# FidoComm.net
KiCad netlist of a schematic drawn in EAGLE
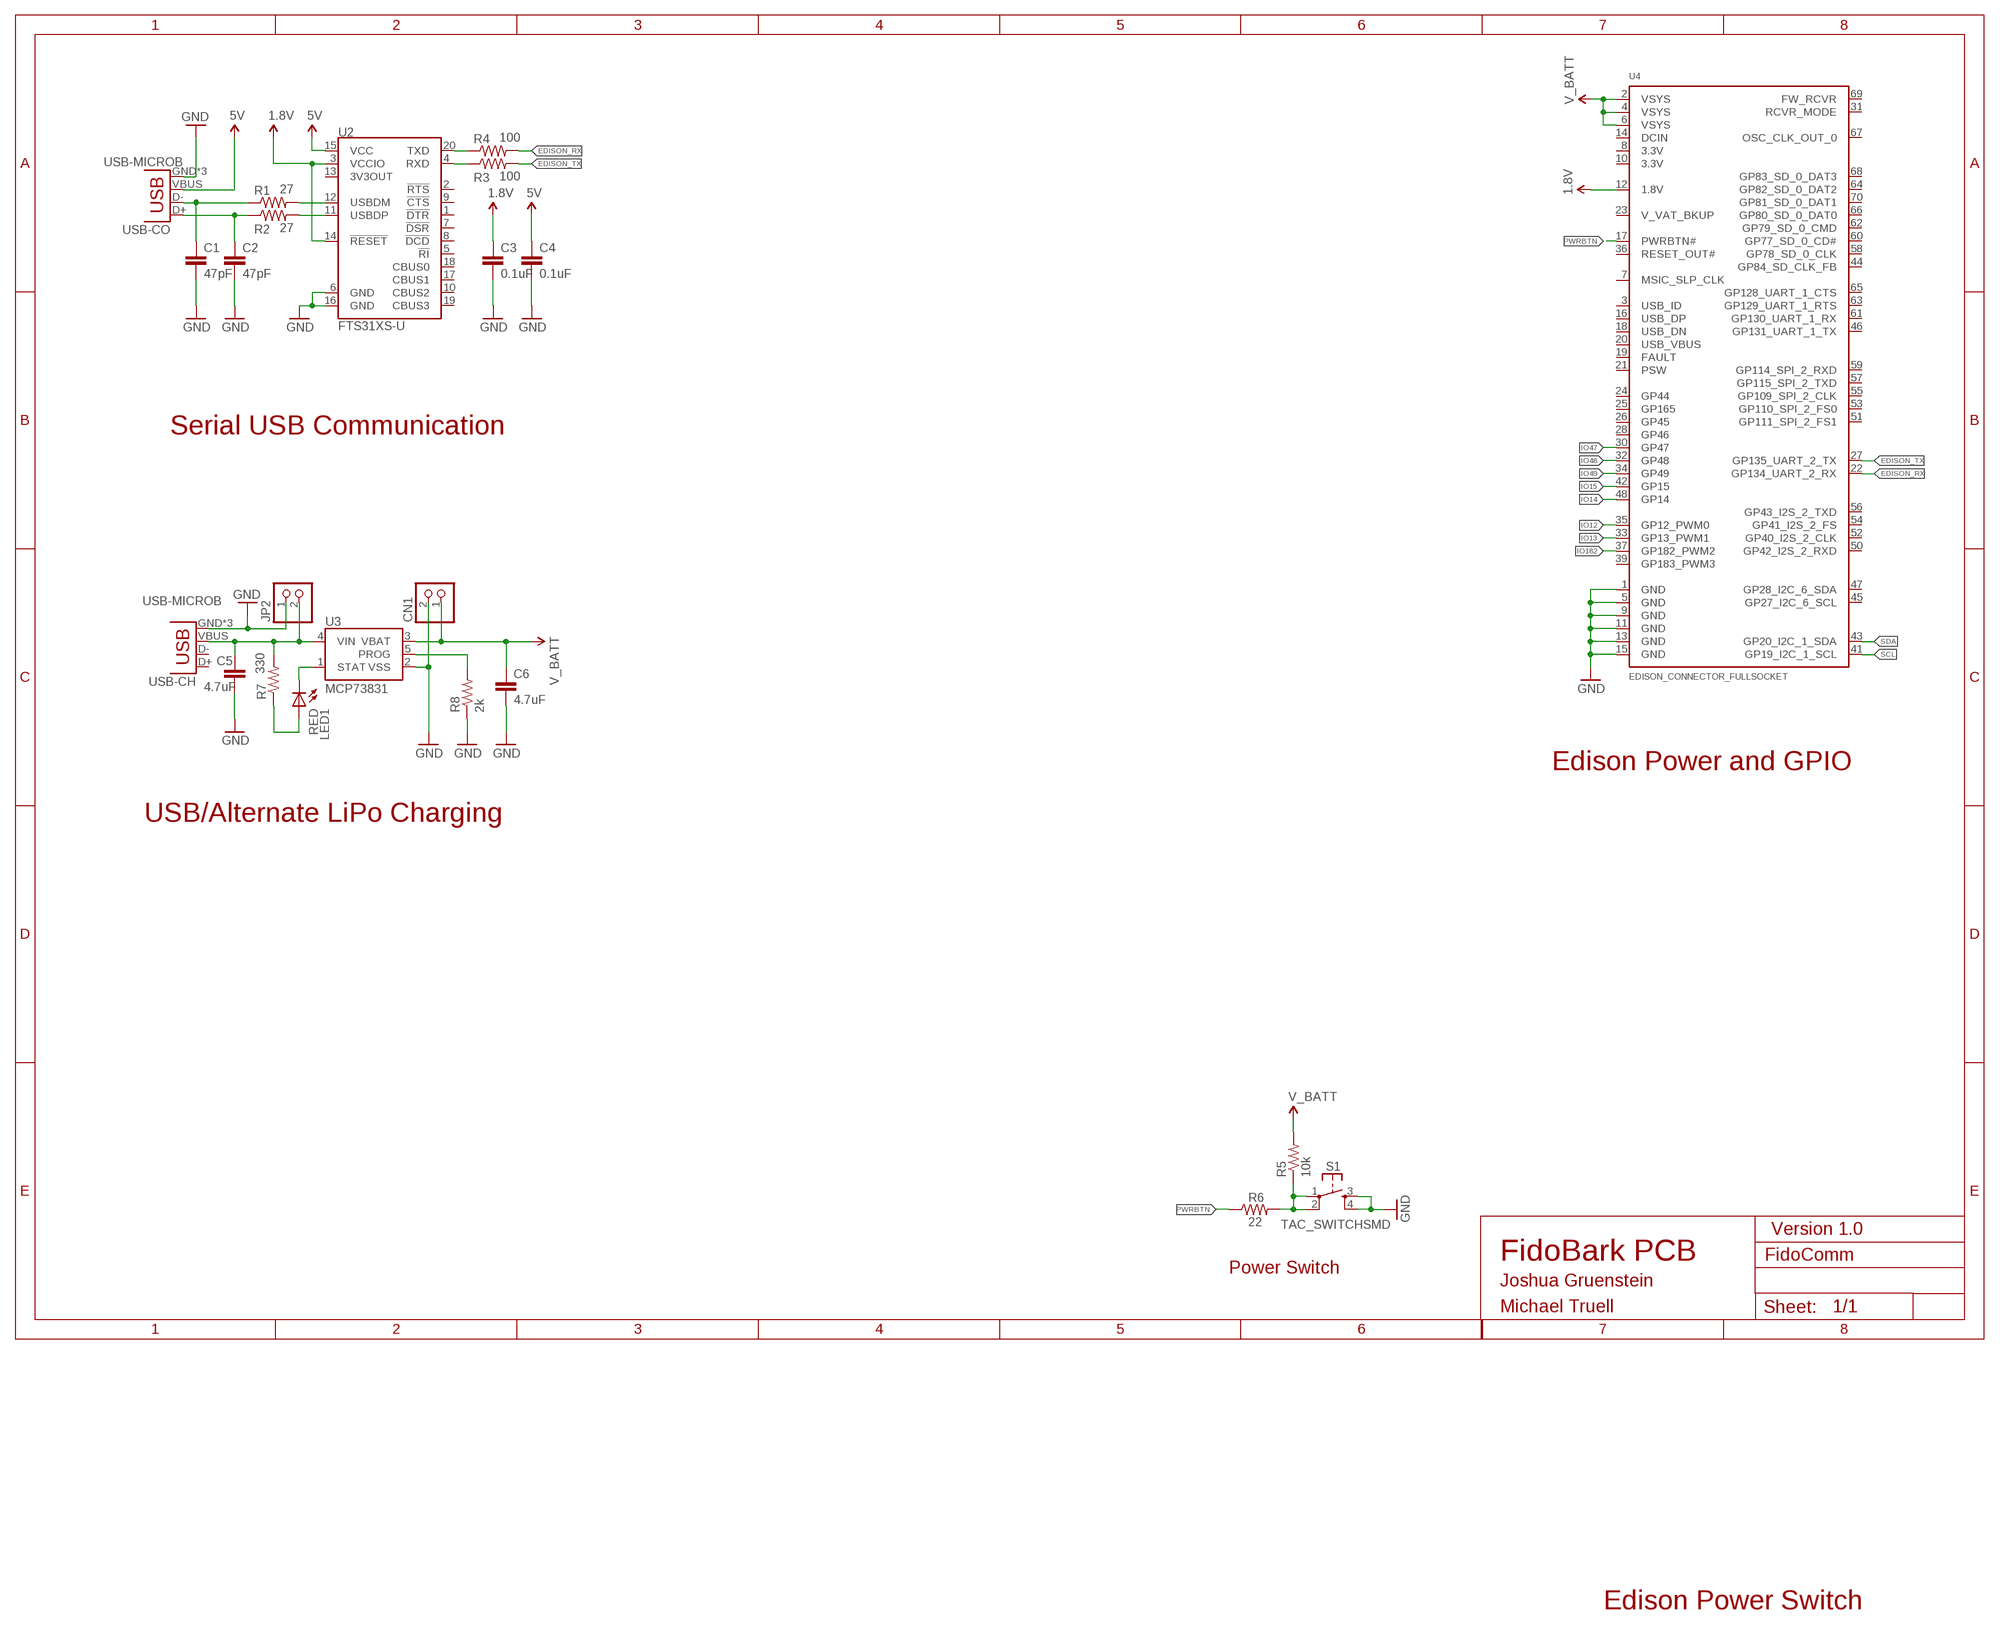
[diagram p0: schematic, sheet 1]

(export (version "E")
  (design (tool "Eeschema 10.0.6"))
  (components
    (comp (ref "C1")
      (value "47pF")
      (footprint "eagle-import:0603-CAP")
      (libsource (lib "eagle-import") (part "CAP0603-CAP"))
    )
    (comp (ref "C2")
      (value "47pF")
      (footprint "eagle-import:0603-CAP")
      (libsource (lib "eagle-import") (part "CAP0603-CAP"))
    )
    (comp (ref "C3")
      (value "0.1uF")
      (footprint "eagle-import:0603-CAP")
      (libsource (lib "eagle-import") (part "CAP0603-CAP"))
    )
    (comp (ref "C4")
      (value "0.1uF")
      (footprint "eagle-import:0603-CAP")
      (libsource (lib "eagle-import") (part "CAP0603-CAP"))
    )
    (comp (ref "C5")
      (value "4.7uF")
      (footprint "eagle-import:0603-CAP")
      (libsource (lib "eagle-import") (part "CAP0603-CAP"))
    )
    (comp (ref "C6")
      (value "4.7uF")
      (footprint "eagle-import:0603-CAP")
      (libsource (lib "eagle-import") (part "CAP0603-CAP"))
    )
    (comp (ref "CN1")
      (value "JST_2PIN-SMT-RA")
      (footprint "eagle-import:JST-PH-2-SMT-RA")
      (libsource (lib "eagle-import") (part "JST_2PIN-SMT-RA"))
    )
    (comp (ref "JP2")
      (value "PINHD-1X2")
      (footprint "eagle-import:1X02")
      (libsource (lib "eagle-import") (part "PINHD-1X2"))
    )
    (comp (ref "LED1")
      (value "RED")
      (footprint "eagle-import:CHIP-LED0603")
      (libsource (lib "eagle-import") (part "LEDCHIP-LED0603"))
    )
    (comp (ref "R1")
      (value "27")
      (footprint "eagle-import:R0603")
      (libsource (lib "eagle-import") (part "R-US_R0603"))
    )
    (comp (ref "R2")
      (value "27")
      (footprint "eagle-import:R0603")
      (libsource (lib "eagle-import") (part "R-US_R0603"))
    )
    (comp (ref "R3")
      (value "100")
      (footprint "eagle-import:R0603")
      (libsource (lib "eagle-import") (part "R-US_R0603"))
    )
    (comp (ref "R4")
      (value "100")
      (footprint "eagle-import:R0603")
      (libsource (lib "eagle-import") (part "R-US_R0603"))
    )
    (comp (ref "R5")
      (value "10k")
      (footprint "eagle-import:R0603")
      (libsource (lib "eagle-import") (part "R-US_R0603"))
    )
    (comp (ref "R6")
      (value "22")
      (footprint "eagle-import:R0603")
      (libsource (lib "eagle-import") (part "R-US_R0603"))
    )
    (comp (ref "R7")
      (value "330")
      (footprint "eagle-import:R0603")
      (libsource (lib "eagle-import") (part "R-US_R0603"))
    )
    (comp (ref "R8")
      (value "2k")
      (footprint "eagle-import:R0603")
      (libsource (lib "eagle-import") (part "R-US_R0603"))
    )
    (comp (ref "S1")
      (value "TAC_SWITCHSMD")
      (footprint "eagle-import:TACTILE-SWITCH-SMD")
      (libsource (lib "eagle-import") (part "TAC_SWITCHSMD"))
    )
    (comp (ref "U2")
      (value "FTS31XS-U")
      (footprint "eagle-import:SSOP20_L")
      (libsource (lib "eagle-import") (part "FT231XS"))
    )
    (comp (ref "U3")
      (value "MCP73831")
      (footprint "eagle-import:SOT23-5")
      (libsource (lib "eagle-import") (part "MCP73831"))
    )
    (comp (ref "U4")
      (value "EDISON_CONNECTOR_FULLSOCKET")
      (footprint "eagle-import:DF40-XC-(X.X)-70DS-0.4V(51)")
      (libsource (lib "eagle-import") (part "EDISON_CONNECTOR_FULLSOCKET"))
    )
    (comp (ref "USB-CH")
      (value "USB-MICROB")
      (footprint "eagle-import:USB-MICROB")
      (libsource (lib "eagle-import") (part "USB-MICROB"))
    )
    (comp (ref "USB-CO")
      (value "USB-MICROB")
      (footprint "eagle-import:USB-MICROB")
      (libsource (lib "eagle-import") (part "USB-MICROB"))
    )
  )
  (nets
    (net (code "1") (name "1.8V") (class "Default")
      (node (ref "C3") (pin "1") (pinfunction "1_1") (pintype "passive"))
      (node (ref "U2") (pin "14") (pinfunction "~{RESET}_14") (pintype "bidirectional"))
      (node (ref "U2") (pin "3") (pinfunction "VCCIO_3") (pintype "bidirectional"))
      (node (ref "U4") (pin "12") (pinfunction "1.8V_12") (pintype "bidirectional"))
    )
    (net (code "2") (name "5V") (class "Default")
      (node (ref "C4") (pin "1") (pinfunction "1_1") (pintype "passive"))
      (node (ref "U2") (pin "15") (pinfunction "VCC_15") (pintype "bidirectional"))
      (node (ref "USB-CO") (pin "VBUS") (pinfunction "VBUS_VBUS") (pintype "bidirectional"))
    )
    (net (code "3") (name "EDISON_RX") (class "Default")
      (node (ref "R4") (pin "2") (pinfunction "2_2") (pintype "passive"))
      (node (ref "U4") (pin "22") (pinfunction "GP134_UART_2_RX_22") (pintype "bidirectional"))
    )
    (net (code "4") (name "EDISON_TX") (class "Default")
      (node (ref "R3") (pin "2") (pinfunction "2_2") (pintype "passive"))
      (node (ref "U4") (pin "27") (pinfunction "GP135_UART_2_TX_27") (pintype "bidirectional"))
    )
    (net (code "5") (name "GND") (class "Default")
      (node (ref "C1") (pin "2") (pinfunction "2_2") (pintype "passive"))
      (node (ref "C2") (pin "2") (pinfunction "2_2") (pintype "passive"))
      (node (ref "C3") (pin "2") (pinfunction "2_2") (pintype "passive"))
      (node (ref "C4") (pin "2") (pinfunction "2_2") (pintype "passive"))
      (node (ref "C5") (pin "2") (pinfunction "2_2") (pintype "passive"))
      (node (ref "C6") (pin "2") (pinfunction "2_2") (pintype "passive"))
      (node (ref "CN1") (pin "2") (pinfunction "1_2") (pintype "passive"))
      (node (ref "JP2") (pin "1") (pinfunction "1_1") (pintype "passive"))
      (node (ref "R8") (pin "1") (pinfunction "1_1") (pintype "passive"))
      (node (ref "S1") (pin "3") (pinfunction "3_3") (pintype "passive"))
      (node (ref "S1") (pin "4") (pinfunction "4_4") (pintype "passive"))
      (node (ref "U2") (pin "16") (pinfunction "GND_16") (pintype "bidirectional"))
      (node (ref "U2") (pin "6") (pinfunction "GND_6") (pintype "bidirectional"))
      (node (ref "U3") (pin "2") (pinfunction "VSS_2") (pintype "power_in"))
      (node (ref "U4") (pin "1") (pinfunction "GND_1") (pintype "bidirectional"))
      (node (ref "U4") (pin "11") (pinfunction "GND_11") (pintype "bidirectional"))
      (node (ref "U4") (pin "13") (pinfunction "GND_13") (pintype "bidirectional"))
      (node (ref "U4") (pin "15") (pinfunction "GND_15") (pintype "bidirectional"))
      (node (ref "U4") (pin "5") (pinfunction "GND_5") (pintype "bidirectional"))
      (node (ref "U4") (pin "9") (pinfunction "GND_9") (pintype "bidirectional"))
      (node (ref "USB-CH") (pin "GND") (pinfunction "GND_GND") (pintype "bidirectional"))
      (node (ref "USB-CH") (pin "MT1") (pinfunction "GND_MT1") (pintype "bidirectional"))
      (node (ref "USB-CH") (pin "MT2") (pinfunction "GND_MT2") (pintype "bidirectional"))
      (node (ref "USB-CO") (pin "GND") (pinfunction "GND_GND") (pintype "bidirectional"))
      (node (ref "USB-CO") (pin "MT1") (pinfunction "GND_MT1") (pintype "bidirectional"))
      (node (ref "USB-CO") (pin "MT2") (pinfunction "GND_MT2") (pintype "bidirectional"))
    )
    (net (code "6") (name "IO12") (class "Default")
      (node (ref "U4") (pin "35") (pinfunction "GP12_PWM0_35") (pintype "bidirectional"))
    )
    (net (code "7") (name "IO13") (class "Default")
      (node (ref "U4") (pin "33") (pinfunction "GP13_PWM1_33") (pintype "bidirectional"))
    )
    (net (code "8") (name "IO14") (class "Default")
      (node (ref "U4") (pin "48") (pinfunction "GP14_48") (pintype "bidirectional"))
    )
    (net (code "9") (name "IO15") (class "Default")
      (node (ref "U4") (pin "42") (pinfunction "GP15_42") (pintype "bidirectional"))
    )
    (net (code "10") (name "IO47") (class "Default")
      (node (ref "U4") (pin "30") (pinfunction "GP47_30") (pintype "bidirectional"))
    )
    (net (code "11") (name "IO48") (class "Default")
      (node (ref "U4") (pin "32") (pinfunction "GP48_32") (pintype "bidirectional"))
    )
    (net (code "12") (name "IO49") (class "Default")
      (node (ref "U4") (pin "34") (pinfunction "GP49_34") (pintype "bidirectional"))
    )
    (net (code "13") (name "IO182") (class "Default")
      (node (ref "U4") (pin "37") (pinfunction "GP182_PWM2_37") (pintype "bidirectional"))
    )
    (net (code "14") (name "Net-(C1-Pad1)") (class "Default")
      (node (ref "C1") (pin "1") (pinfunction "1_1") (pintype "passive"))
      (node (ref "R1") (pin "1") (pinfunction "1_1") (pintype "passive"))
      (node (ref "USB-CO") (pin "D-") (pinfunction "D-_D-") (pintype "bidirectional"))
    )
    (net (code "15") (name "Net-(C2-Pad1)") (class "Default")
      (node (ref "C2") (pin "1") (pinfunction "1_1") (pintype "passive"))
      (node (ref "R2") (pin "1") (pinfunction "1_1") (pintype "passive"))
      (node (ref "USB-CO") (pin "D+") (pinfunction "D+_D+") (pintype "bidirectional"))
    )
    (net (code "16") (name "Net-(LED1-PadA)") (class "Default")
      (node (ref "LED1") (pin "A") (pinfunction "A_A") (pintype "passive"))
      (node (ref "R7") (pin "1") (pinfunction "1_1") (pintype "passive"))
    )
    (net (code "17") (name "Net-(R5-Pad1)") (class "Default")
      (node (ref "R5") (pin "1") (pinfunction "1_1") (pintype "passive"))
      (node (ref "R6") (pin "2") (pinfunction "2_2") (pintype "passive"))
      (node (ref "S1") (pin "1") (pinfunction "1_1") (pintype "passive"))
      (node (ref "S1") (pin "2") (pinfunction "2_2") (pintype "passive"))
    )
    (net (code "18") (name "Net-(U2-RXD)") (class "Default")
      (node (ref "R3") (pin "1") (pinfunction "1_1") (pintype "passive"))
      (node (ref "U2") (pin "4") (pinfunction "RXD_4") (pintype "bidirectional"))
    )
    (net (code "19") (name "Net-(U2-TXD)") (class "Default")
      (node (ref "R4") (pin "1") (pinfunction "1_1") (pintype "passive"))
      (node (ref "U2") (pin "20") (pinfunction "TXD_20") (pintype "bidirectional"))
    )
    (net (code "20") (name "Net-(U2-USBDM)") (class "Default")
      (node (ref "R1") (pin "2") (pinfunction "2_2") (pintype "passive"))
      (node (ref "U2") (pin "12") (pinfunction "USBDM_12") (pintype "bidirectional"))
    )
    (net (code "21") (name "Net-(U2-USBDP)") (class "Default")
      (node (ref "R2") (pin "2") (pinfunction "2_2") (pintype "passive"))
      (node (ref "U2") (pin "11") (pinfunction "USBDP_11") (pintype "bidirectional"))
    )
    (net (code "22") (name "Net-(U3-PROG)") (class "Default")
      (node (ref "R8") (pin "2") (pinfunction "2_2") (pintype "passive"))
      (node (ref "U3") (pin "5") (pinfunction "PROG_5") (pintype "input"))
    )
    (net (code "23") (name "Net-(U3-STAT)") (class "Default")
      (node (ref "LED1") (pin "C") (pinfunction "C_C") (pintype "passive"))
      (node (ref "U3") (pin "1") (pinfunction "STAT_1") (pintype "output"))
    )
    (net (code "24") (name "Net-(U3-VIN)") (class "Default")
      (node (ref "C5") (pin "1") (pinfunction "1_1") (pintype "passive"))
      (node (ref "JP2") (pin "2") (pinfunction "2_2") (pintype "passive"))
      (node (ref "R7") (pin "2") (pinfunction "2_2") (pintype "passive"))
      (node (ref "U3") (pin "4") (pinfunction "VIN_4") (pintype "power_in"))
      (node (ref "USB-CH") (pin "VBUS") (pinfunction "VBUS_VBUS") (pintype "bidirectional"))
    )
    (net (code "25") (name "PWRBTN") (class "Default")
      (node (ref "R6") (pin "1") (pinfunction "1_1") (pintype "passive"))
      (node (ref "U4") (pin "17") (pinfunction "PWRBTN#_17") (pintype "bidirectional"))
    )
    (net (code "26") (name "SCL") (class "Default")
      (node (ref "U4") (pin "41") (pinfunction "GP19_I2C_1_SCL_41") (pintype "bidirectional"))
    )
    (net (code "27") (name "SDA") (class "Default")
      (node (ref "U4") (pin "43") (pinfunction "GP20_I2C_1_SDA_43") (pintype "bidirectional"))
    )
    (net (code "28") (name "V_BATT") (class "Default")
      (node (ref "C6") (pin "1") (pinfunction "1_1") (pintype "passive"))
      (node (ref "CN1") (pin "1") (pinfunction "2_1") (pintype "passive"))
      (node (ref "R5") (pin "2") (pinfunction "2_2") (pintype "passive"))
      (node (ref "U3") (pin "3") (pinfunction "VBAT_3") (pintype "power_in"))
      (node (ref "U4") (pin "2") (pinfunction "VSYS_2") (pintype "bidirectional"))
      (node (ref "U4") (pin "4") (pinfunction "VSYS_4") (pintype "bidirectional"))
      (node (ref "U4") (pin "6") (pinfunction "VSYS_6") (pintype "bidirectional"))
    )
    (net (code "29") (name "unconnected-(U2-3V3OUT-Pad13)") (class "Default")
      (node (ref "U2") (pin "13") (pinfunction "3V3OUT_13") (pintype "bidirectional"))
    )
    (net (code "30") (name "unconnected-(U2-CBUS0-Pad18)") (class "Default")
      (node (ref "U2") (pin "18") (pinfunction "CBUS0_18") (pintype "bidirectional"))
    )
    (net (code "31") (name "unconnected-(U2-CBUS1-Pad17)") (class "Default")
      (node (ref "U2") (pin "17") (pinfunction "CBUS1_17") (pintype "bidirectional"))
    )
    (net (code "32") (name "unconnected-(U2-CBUS2-Pad10)") (class "Default")
      (node (ref "U2") (pin "10") (pinfunction "CBUS2_10") (pintype "bidirectional"))
    )
    (net (code "33") (name "unconnected-(U2-CBUS3-Pad19)") (class "Default")
      (node (ref "U2") (pin "19") (pinfunction "CBUS3_19") (pintype "bidirectional"))
    )
    (net (code "34") (name "unconnected-(U2-~{CTS}-Pad9)") (class "Default")
      (node (ref "U2") (pin "9") (pinfunction "~{CTS}_9") (pintype "bidirectional"))
    )
    (net (code "35") (name "unconnected-(U2-~{DCD}-Pad8)") (class "Default")
      (node (ref "U2") (pin "8") (pinfunction "~{DCD}_8") (pintype "bidirectional"))
    )
    (net (code "36") (name "unconnected-(U2-~{DSR}-Pad7)") (class "Default")
      (node (ref "U2") (pin "7") (pinfunction "~{DSR}_7") (pintype "bidirectional"))
    )
    (net (code "37") (name "unconnected-(U2-~{DTR}-Pad1)") (class "Default")
      (node (ref "U2") (pin "1") (pinfunction "~{DTR}_1") (pintype "bidirectional"))
    )
    (net (code "38") (name "unconnected-(U2-~{RI}-Pad5)") (class "Default")
      (node (ref "U2") (pin "5") (pinfunction "~{RI}_5") (pintype "bidirectional"))
    )
    (net (code "39") (name "unconnected-(U2-~{RTS}-Pad2)") (class "Default")
      (node (ref "U2") (pin "2") (pinfunction "~{RTS}_2") (pintype "bidirectional"))
    )
    (net (code "40") (name "unconnected-(U4-3.3V-Pad8)") (class "Default")
      (node (ref "U4") (pin "8") (pinfunction "3.3V_8") (pintype "bidirectional"))
    )
    (net (code "41") (name "unconnected-(U4-3.3V-Pad10)") (class "Default")
      (node (ref "U4") (pin "10") (pinfunction "3.3V_10") (pintype "bidirectional"))
    )
    (net (code "42") (name "unconnected-(U4-DCIN-Pad14)") (class "Default")
      (node (ref "U4") (pin "14") (pinfunction "DCIN_14") (pintype "bidirectional"))
    )
    (net (code "43") (name "unconnected-(U4-FAULT-Pad19)") (class "Default")
      (node (ref "U4") (pin "19") (pinfunction "FAULT_19") (pintype "bidirectional"))
    )
    (net (code "44") (name "unconnected-(U4-FW_RCVR-Pad69)") (class "Default")
      (node (ref "U4") (pin "69") (pinfunction "FW_RCVR_69") (pintype "bidirectional"))
    )
    (net (code "45") (name "unconnected-(U4-GP27_I2C_6_SCL-Pad45)") (class "Default")
      (node (ref "U4") (pin "45") (pinfunction "GP27_I2C_6_SCL_45") (pintype "bidirectional"))
    )
    (net (code "46") (name "unconnected-(U4-GP28_I2C_6_SDA-Pad47)") (class "Default")
      (node (ref "U4") (pin "47") (pinfunction "GP28_I2C_6_SDA_47") (pintype "bidirectional"))
    )
    (net (code "47") (name "unconnected-(U4-GP40_I2S_2_CLK-Pad52)") (class "Default")
      (node (ref "U4") (pin "52") (pinfunction "GP40_I2S_2_CLK_52") (pintype "bidirectional"))
    )
    (net (code "48") (name "unconnected-(U4-GP41_I2S_2_FS-Pad54)") (class "Default")
      (node (ref "U4") (pin "54") (pinfunction "GP41_I2S_2_FS_54") (pintype "bidirectional"))
    )
    (net (code "49") (name "unconnected-(U4-GP42_I2S_2_RXD-Pad50)") (class "Default")
      (node (ref "U4") (pin "50") (pinfunction "GP42_I2S_2_RXD_50") (pintype "bidirectional"))
    )
    (net (code "50") (name "unconnected-(U4-GP43_I2S_2_TXD-Pad56)") (class "Default")
      (node (ref "U4") (pin "56") (pinfunction "GP43_I2S_2_TXD_56") (pintype "bidirectional"))
    )
    (net (code "51") (name "unconnected-(U4-GP44-Pad24)") (class "Default")
      (node (ref "U4") (pin "24") (pinfunction "GP44_24") (pintype "bidirectional"))
    )
    (net (code "52") (name "unconnected-(U4-GP45-Pad26)") (class "Default")
      (node (ref "U4") (pin "26") (pinfunction "GP45_26") (pintype "bidirectional"))
    )
    (net (code "53") (name "unconnected-(U4-GP46-Pad28)") (class "Default")
      (node (ref "U4") (pin "28") (pinfunction "GP46_28") (pintype "bidirectional"))
    )
    (net (code "54") (name "unconnected-(U4-GP77_SD_0_CD#-Pad60)") (class "Default")
      (node (ref "U4") (pin "60") (pinfunction "GP77_SD_0_CD#_60") (pintype "bidirectional"))
    )
    (net (code "55") (name "unconnected-(U4-GP78_SD_0_CLK-Pad58)") (class "Default")
      (node (ref "U4") (pin "58") (pinfunction "GP78_SD_0_CLK_58") (pintype "bidirectional"))
    )
    (net (code "56") (name "unconnected-(U4-GP79_SD_0_CMD-Pad62)") (class "Default")
      (node (ref "U4") (pin "62") (pinfunction "GP79_SD_0_CMD_62") (pintype "bidirectional"))
    )
    (net (code "57") (name "unconnected-(U4-GP80_SD_0_DAT0-Pad66)") (class "Default")
      (node (ref "U4") (pin "66") (pinfunction "GP80_SD_0_DAT0_66") (pintype "bidirectional"))
    )
    (net (code "58") (name "unconnected-(U4-GP81_SD_0_DAT1-Pad70)") (class "Default")
      (node (ref "U4") (pin "70") (pinfunction "GP81_SD_0_DAT1_70") (pintype "bidirectional"))
    )
    (net (code "59") (name "unconnected-(U4-GP82_SD_0_DAT2-Pad64)") (class "Default")
      (node (ref "U4") (pin "64") (pinfunction "GP82_SD_0_DAT2_64") (pintype "bidirectional"))
    )
    (net (code "60") (name "unconnected-(U4-GP83_SD_0_DAT3-Pad68)") (class "Default")
      (node (ref "U4") (pin "68") (pinfunction "GP83_SD_0_DAT3_68") (pintype "bidirectional"))
    )
    (net (code "61") (name "unconnected-(U4-GP84_SD_CLK_FB-Pad44)") (class "Default")
      (node (ref "U4") (pin "44") (pinfunction "GP84_SD_CLK_FB_44") (pintype "bidirectional"))
    )
    (net (code "62") (name "unconnected-(U4-GP109_SPI_2_CLK-Pad55)") (class "Default")
      (node (ref "U4") (pin "55") (pinfunction "GP109_SPI_2_CLK_55") (pintype "bidirectional"))
    )
    (net (code "63") (name "unconnected-(U4-GP110_SPI_2_FS0-Pad53)") (class "Default")
      (node (ref "U4") (pin "53") (pinfunction "GP110_SPI_2_FS0_53") (pintype "bidirectional"))
    )
    (net (code "64") (name "unconnected-(U4-GP111_SPI_2_FS1-Pad51)") (class "Default")
      (node (ref "U4") (pin "51") (pinfunction "GP111_SPI_2_FS1_51") (pintype "bidirectional"))
    )
    (net (code "65") (name "unconnected-(U4-GP114_SPI_2_RXD-Pad59)") (class "Default")
      (node (ref "U4") (pin "59") (pinfunction "GP114_SPI_2_RXD_59") (pintype "bidirectional"))
    )
    (net (code "66") (name "unconnected-(U4-GP115_SPI_2_TXD-Pad57)") (class "Default")
      (node (ref "U4") (pin "57") (pinfunction "GP115_SPI_2_TXD_57") (pintype "bidirectional"))
    )
    (net (code "67") (name "unconnected-(U4-GP128_UART_1_CTS-Pad65)") (class "Default")
      (node (ref "U4") (pin "65") (pinfunction "GP128_UART_1_CTS_65") (pintype "bidirectional"))
    )
    (net (code "68") (name "unconnected-(U4-GP129_UART_1_RTS-Pad63)") (class "Default")
      (node (ref "U4") (pin "63") (pinfunction "GP129_UART_1_RTS_63") (pintype "bidirectional"))
    )
    (net (code "69") (name "unconnected-(U4-GP130_UART_1_RX-Pad61)") (class "Default")
      (node (ref "U4") (pin "61") (pinfunction "GP130_UART_1_RX_61") (pintype "bidirectional"))
    )
    (net (code "70") (name "unconnected-(U4-GP131_UART_1_TX-Pad46)") (class "Default")
      (node (ref "U4") (pin "46") (pinfunction "GP131_UART_1_TX_46") (pintype "bidirectional"))
    )
    (net (code "71") (name "unconnected-(U4-GP165-Pad25)") (class "Default")
      (node (ref "U4") (pin "25") (pinfunction "GP165_25") (pintype "bidirectional"))
    )
    (net (code "72") (name "unconnected-(U4-GP183_PWM3-Pad39)") (class "Default")
      (node (ref "U4") (pin "39") (pinfunction "GP183_PWM3_39") (pintype "bidirectional"))
    )
    (net (code "73") (name "unconnected-(U4-MSIC_SLP_CLK-Pad7)") (class "Default")
      (node (ref "U4") (pin "7") (pinfunction "MSIC_SLP_CLK_7") (pintype "bidirectional"))
    )
    (net (code "74") (name "unconnected-(U4-OSC_CLK_OUT_0-Pad67)") (class "Default")
      (node (ref "U4") (pin "67") (pinfunction "OSC_CLK_OUT_0_67") (pintype "bidirectional"))
    )
    (net (code "75") (name "unconnected-(U4-PSW-Pad21)") (class "Default")
      (node (ref "U4") (pin "21") (pinfunction "PSW_21") (pintype "bidirectional"))
    )
    (net (code "76") (name "unconnected-(U4-RCVR_MODE-Pad31)") (class "Default")
      (node (ref "U4") (pin "31") (pinfunction "RCVR_MODE_31") (pintype "bidirectional"))
    )
    (net (code "77") (name "unconnected-(U4-RESET_OUT#-Pad36)") (class "Default")
      (node (ref "U4") (pin "36") (pinfunction "RESET_OUT#_36") (pintype "bidirectional"))
    )
    (net (code "78") (name "unconnected-(U4-USB_DN-Pad18)") (class "Default")
      (node (ref "U4") (pin "18") (pinfunction "USB_DN_18") (pintype "bidirectional"))
    )
    (net (code "79") (name "unconnected-(U4-USB_DP-Pad16)") (class "Default")
      (node (ref "U4") (pin "16") (pinfunction "USB_DP_16") (pintype "bidirectional"))
    )
    (net (code "80") (name "unconnected-(U4-USB_ID-Pad3)") (class "Default")
      (node (ref "U4") (pin "3") (pinfunction "USB_ID_3") (pintype "bidirectional"))
    )
    (net (code "81") (name "unconnected-(U4-USB_VBUS-Pad20)") (class "Default")
      (node (ref "U4") (pin "20") (pinfunction "USB_VBUS_20") (pintype "bidirectional"))
    )
    (net (code "82") (name "unconnected-(U4-V_VAT_BKUP-Pad23)") (class "Default")
      (node (ref "U4") (pin "23") (pinfunction "V_VAT_BKUP_23") (pintype "bidirectional"))
    )
    (net (code "83") (name "unconnected-(USB-CH-PadD+)") (class "Default")
      (node (ref "USB-CH") (pin "D+") (pinfunction "D+_D+") (pintype "bidirectional"))
    )
    (net (code "84") (name "unconnected-(USB-CH-PadD-)") (class "Default")
      (node (ref "USB-CH") (pin "D-") (pinfunction "D-_D-") (pintype "bidirectional"))
    )
  )
)
